# v2-DCSupplyHub.net
KiCad netlist of a schematic drawn in Altium Designer
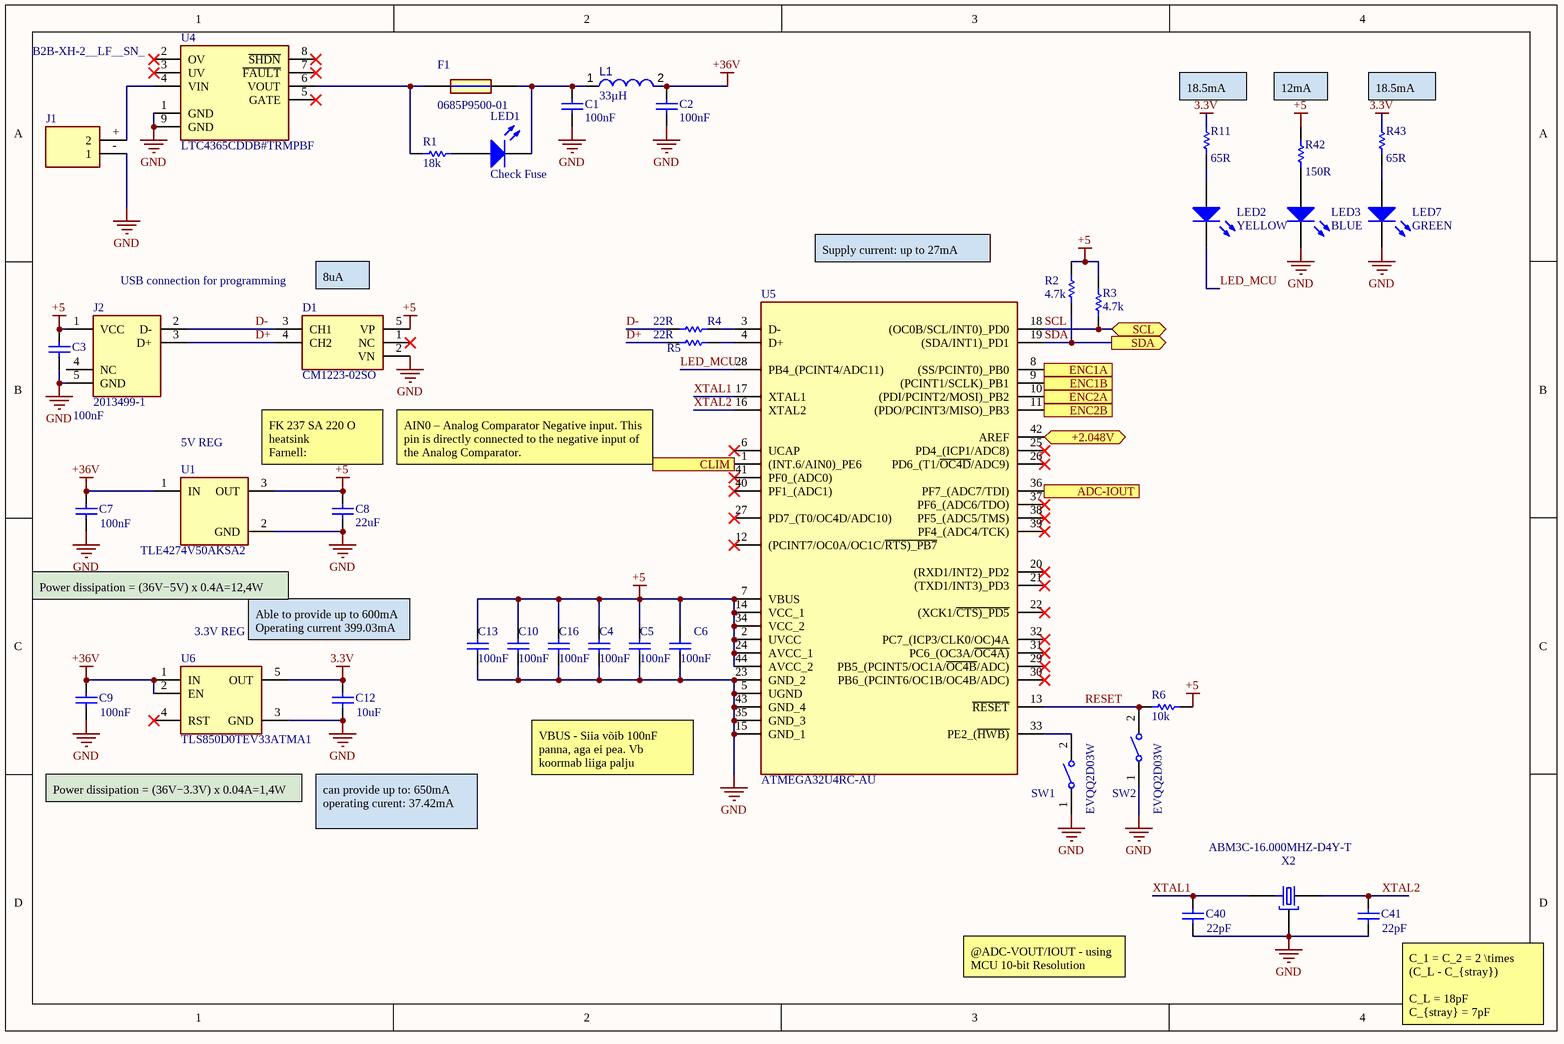
[diagram p0: v2-DCSupplyHub.SchDoc]

(export (version "E")
  (design (tool "Eeschema 10.0.6"))
  (components
    (comp (ref "C1")
      (value "100nF")
      (footprint "Cap_0603")
      (description "Capacitor")
      (fields (field (name "Comment") "Cap") (field (name "PUBLISHER") "Altium Limited"))
      (libsource (lib "cc cv power supply") (part "Cap"))
    )
    (comp (ref "C2")
      (value "100nF")
      (footprint "Cap_0603")
      (description "Capacitor")
      (fields (field (name "Comment") "Cap") (field (name "PUBLISHER") "Altium Limited"))
      (libsource (lib "cc cv power supply") (part "Cap"))
    )
    (comp (ref "C3")
      (value "100nF")
      (footprint "Cap_0603")
      (description "Capacitor")
      (fields (field (name "Comment") "Cap") (field (name "PUBLISHER") "Altium Limited"))
      (libsource (lib "cc cv power supply") (part "Cap"))
    )
    (comp (ref "C4")
      (value "100nF")
      (footprint "Cap_0603")
      (description "Capacitor")
      (fields (field (name "Comment") "Cap") (field (name "PUBLISHER") "Altium Limited"))
      (libsource (lib "cc cv power supply") (part "Cap"))
    )
    (comp (ref "C5")
      (value "100nF")
      (footprint "Cap_0603")
      (description "Capacitor")
      (fields (field (name "Comment") "Cap") (field (name "PUBLISHER") "Altium Limited"))
      (libsource (lib "cc cv power supply") (part "Cap"))
    )
    (comp (ref "C6")
      (value "100nF")
      (footprint "Cap_0603")
      (description "Capacitor")
      (fields (field (name "Comment") "Cap") (field (name "PUBLISHER") "Altium Limited"))
      (libsource (lib "cc cv power supply") (part "Cap"))
    )
    (comp (ref "C7")
      (value "100nF")
      (footprint "Cap_0603")
      (description "Capacitor")
      (fields (field (name "Comment") "Cap") (field (name "PUBLISHER") "Altium Limited"))
      (libsource (lib "cc cv power supply") (part "Cap"))
    )
    (comp (ref "C8")
      (value "22uF")
      (footprint "Cap_0603")
      (description "Capacitor")
      (fields (field (name "Comment") "Cap") (field (name "PUBLISHER") "Altium Limited"))
      (libsource (lib "cc cv power supply") (part "Cap"))
    )
    (comp (ref "C9")
      (value "100nF")
      (footprint "Cap_0603")
      (description "Capacitor")
      (fields (field (name "Comment") "Cap") (field (name "PUBLISHER") "Altium Limited"))
      (libsource (lib "cc cv power supply") (part "Cap"))
    )
    (comp (ref "C10")
      (value "100nF")
      (footprint "Cap_0603")
      (description "Capacitor")
      (fields (field (name "Comment") "Cap") (field (name "PUBLISHER") "Altium Limited"))
      (libsource (lib "cc cv power supply") (part "Cap"))
    )
    (comp (ref "C12")
      (value "10uF")
      (footprint "Cap_0603")
      (description "Capacitor")
      (fields (field (name "Comment") "Cap") (field (name "PUBLISHER") "Altium Limited"))
      (libsource (lib "cc cv power supply") (part "Cap"))
    )
    (comp (ref "C13")
      (value "100nF")
      (footprint "Cap_0603")
      (description "Capacitor")
      (fields (field (name "Comment") "Cap") (field (name "PUBLISHER") "Altium Limited"))
      (libsource (lib "cc cv power supply") (part "Cap"))
    )
    (comp (ref "C16")
      (value "100nF")
      (footprint "Cap_0603")
      (description "Capacitor")
      (fields (field (name "Comment") "Cap") (field (name "PUBLISHER") "Altium Limited"))
      (libsource (lib "cc cv power supply") (part "Cap"))
    )
    (comp (ref "C40")
      (value "22pF")
      (footprint "Cap_0603")
      (description "Capacitor")
      (fields (field (name "Comment") "Cap") (field (name "PUBLISHER") "Altium Limited"))
      (libsource (lib "cc cv power supply") (part "Cap"))
    )
    (comp (ref "C41")
      (value "22pF")
      (footprint "Cap_0603")
      (description "Capacitor")
      (fields (field (name "Comment") "Cap") (field (name "PUBLISHER") "Altium Limited"))
      (libsource (lib "cc cv power supply") (part "Cap"))
    )
    (comp (ref "D1")
      (value "CM1223-02SO")
      (footprint "SamacSys:SOT95P280X145-5N")
      (description "TVS Diode (Uni-directional)")
      (fields (field (name "MOUSER PART NUMBER") "748-CM1223-02SO"))
      (libsource (lib "SamacSys") (part "CM1223-02SO"))
    )
    (comp (ref "F1")
      (value "0685P9500-01")
      (footprint "FUSC3216X83N")
      (description "Fuse Chip Fast Acting 50A 32V SMD Solder Pad 1206 3.2 X 1.58 X 0.63mm Ceramic T/R")
      (libsource (lib "DCSupplyHubLib") (part "0685P9500-01"))
    )
    (comp (ref "J1")
      (value "B2B-XH-2__LF__SN_")
      (footprint "SamacSys:B2BXH2LFSN")
      (description "Connector")
      (fields (field (name "MANUFACTURER_PART_NUMBER") "B2B-XH-2 (LF)(SN)"))
      (libsource (lib "DCSupplyHubLib") (part "B2B-XH-2__LF__SN_"))
    )
    (comp (ref "J2")
      (value "2013499-1")
      (footprint "SamacSys:2013499-1")
      (description "Connector")
      (fields (field (name "MOUSER PART NUMBER") "571-2013499-1"))
      (libsource (lib "SamacSys") (part "2013499-1"))
    )
    (comp (ref "L1")
      (value "33µH")
      (footprint "WE-LQS 4018")
      (description "WE-LQS SMD Power Inductor, L=33 µH")
      (fields (field (name "TOLERANCE") "20%") (field (name "Comment") "74404042330"))
      (libsource (lib "University of Tartu") (part "CMP-001-0020-1"))
    )
    (comp (ref "LED1")
      (value "Check Fuse")
      (footprint "LED_SMD_0805_R")
      (description "Typical RED, GREEN, YELLOW, AMBER GaAs LED")
      (fields (field (name "PUBLISHER") "Altium Limited"))
      (libsource (lib "cc cv power supply") (part "LED2"))
    )
    (comp (ref "LED2")
      (value "YELLOW")
      (footprint "LED_SMD_0805_R")
      (description "Typical RED, GREEN, YELLOW, AMBER GaAs LED")
      (fields (field (name "PUBLISHER") "Altium Limited"))
      (libsource (lib "cc cv power supply") (part "LED2"))
    )
    (comp (ref "LED3")
      (value "BLUE")
      (footprint "LED_SMD_0805_R")
      (description "Typical RED, GREEN, YELLOW, AMBER GaAs LED")
      (fields (field (name "PUBLISHER") "Altium Limited"))
      (libsource (lib "cc cv power supply") (part "LED2"))
    )
    (comp (ref "LED7")
      (value "GREEN")
      (footprint "LED_SMD_0805_R")
      (description "Typical RED, GREEN, YELLOW, AMBER GaAs LED")
      (fields (field (name "PUBLISHER") "Altium Limited"))
      (libsource (lib "cc cv power supply") (part "LED2"))
    )
    (comp (ref "R1")
      (value "18k")
      (footprint "RES_0805")
      (description "Resistor")
      (fields (field (name "Comment") "Res1") (field (name "PUBLISHER") "Altium Limited"))
      (libsource (lib "cc cv power supply") (part "Res1"))
    )
    (comp (ref "R2")
      (value "4.7k")
      (footprint "RES_0805")
      (description "Resistor")
      (fields (field (name "Comment") "Res1") (field (name "PUBLISHER") "Altium Limited"))
      (libsource (lib "cc cv power supply") (part "Res1"))
    )
    (comp (ref "R3")
      (value "4.7k")
      (footprint "RES_0805")
      (description "Resistor")
      (fields (field (name "Comment") "Res1") (field (name "PUBLISHER") "Altium Limited"))
      (libsource (lib "cc cv power supply") (part "Res1"))
    )
    (comp (ref "R4")
      (value "22R")
      (footprint "RES_0805")
      (description "Resistor")
      (fields (field (name "Comment") "Res1") (field (name "PUBLISHER") "Altium Limited"))
      (libsource (lib "cc cv power supply") (part "Res1"))
    )
    (comp (ref "R5")
      (value "22R")
      (footprint "RES_0805")
      (description "Resistor")
      (fields (field (name "Comment") "Res1") (field (name "PUBLISHER") "Altium Limited"))
      (libsource (lib "cc cv power supply") (part "Res1"))
    )
    (comp (ref "R6")
      (value "10k")
      (footprint "RES_0805")
      (description "Resistor")
      (fields (field (name "Comment") "Res1") (field (name "PUBLISHER") "Altium Limited"))
      (libsource (lib "cc cv power supply") (part "Res1"))
    )
    (comp (ref "R11")
      (value "65R")
      (footprint "RES_0805")
      (description "Resistor")
      (fields (field (name "Comment") "Res1") (field (name "PUBLISHER") "Altium Limited"))
      (libsource (lib "cc cv power supply") (part "Res1"))
    )
    (comp (ref "R42")
      (value "150R")
      (footprint "RES_0805")
      (description "Resistor")
      (fields (field (name "Comment") "Res1") (field (name "PUBLISHER") "Altium Limited"))
      (libsource (lib "cc cv power supply") (part "Res1"))
    )
    (comp (ref "R43")
      (value "65R")
      (footprint "RES_0805")
      (description "Resistor")
      (fields (field (name "Comment") "Res1") (field (name "PUBLISHER") "Altium Limited"))
      (libsource (lib "cc cv power supply") (part "Res1"))
    )
    (comp (ref "SW1")
      (value "EVQQ2D03W")
      (footprint "EVQQ2D03W")
      (description "FSMSM Push Button Switch, 50 mA, -35 to 85 degC, 2-Pin SMD, RoHS, Tape and Reel")
      (fields (field (name "MANUFACTURER") "TE Connectivity"))
      (libsource (lib "DCSupplyHubLib") (part "SW-SPST-2_C"))
    )
    (comp (ref "SW2")
      (value "EVQQ2D03W")
      (footprint "EVQQ2D03W")
      (description "FSMSM Push Button Switch, 50 mA, -35 to 85 degC, 2-Pin SMD, RoHS, Tape and Reel")
      (fields (field (name "MANUFACTURER") "TE Connectivity"))
      (libsource (lib "DCSupplyHubLib") (part "SW-SPST-2_C"))
    )
    (comp (ref "U1")
      (value "TLE4274V50AKSA2")
      (footprint "TO254P440X1000X2110-3P")
      (description "LDO, FIXED, 5V, 0.4A, -40 TO 150DEG C")
      (fields
        (field (name "MANUFACTURER_PART_NUMBER") "TLE4274DV50ATMA2")
        (field (name "MOUSER PART NUMBER") "726-TLE4274DV50ATMA2")
      )
      (libsource (lib "SamacSys") (part "TLE4274DV50ATMA2"))
    )
    (comp (ref "U4")
      (value "LTC4365CDDB#PBF")
      (footprint "SamacSys:SON50P200X300X80-9N-D")
      (description "vervoltage, Undervoltage and Reverse Supply Protection Controller")
      (fields (field (name "MOUSER PART NUMBER") "584-LTC4365CDDB#PBF"))
      (libsource (lib "DCSupplyHubLib") (part "LTC4365CDDB#PBF"))
    )
    (comp (ref "U5")
      (value "ATMEGA32U4-AU")
      (footprint "QFP80P1200X1200X120-44N")
      (fields (field (name "MOUSER PART NUMBER") "556-ATMEGA32U4-AU"))
      (libsource (lib "DCSupplyHubLib") (part "ATMEGA32U4-AU"))
    )
    (comp (ref "U6")
      (value "TLS850D0TEV33ATMA1")
      (footprint "SamacSys:BTS6143D")
      (description "LDO VOltage regulator")
      (fields (field (name "MOUSER PART NUMBER") "726-TLS850D0TEV33ATM"))
      (libsource (lib "SamacSys") (part "TLS850D0TEV33ATMA1"))
    )
    (comp (ref "X2")
      (value "ABM3C-16.000MHZ-D4Y-T")
      (footprint "ABM3C16000MHZD4YT")
      (description "16MHz Â±30ppm Crystal 18pF 50 Ohms 4-SMD, No Lead")
      (fields (field (name "MF") "Abracon"))
      (libsource (lib "cc cv power supply") (part "ABM3C-16.000MHZ-D4Y-T"))
    )
  )
  (nets
    (net (code "1") (name "+5") (class "Default")
      (node (ref "C10") (pin "2") (pinfunction "2_2") (pintype "passive"))
      (node (ref "C13") (pin "2") (pinfunction "2_2") (pintype "passive"))
      (node (ref "C16") (pin "2") (pinfunction "2_2") (pintype "passive"))
      (node (ref "C3") (pin "2") (pinfunction "2_2") (pintype "passive"))
      (node (ref "C4") (pin "2") (pinfunction "2_2") (pintype "passive"))
      (node (ref "C5") (pin "2") (pinfunction "2_2") (pintype "passive"))
      (node (ref "C6") (pin "2") (pinfunction "2_2") (pintype "passive"))
      (node (ref "C8") (pin "1") (pinfunction "1_1") (pintype "passive"))
      (node (ref "D1") (pin "5") (pinfunction "VP_5") (pintype "passive"))
      (node (ref "J2") (pin "1") (pinfunction "VCC_1") (pintype "passive"))
      (node (ref "R2") (pin "2") (pinfunction "2_2") (pintype "passive"))
      (node (ref "R3") (pin "2") (pinfunction "2_2") (pintype "passive"))
      (node (ref "R42") (pin "1") (pinfunction "1_1") (pintype "passive"))
      (node (ref "R6") (pin "1") (pinfunction "1_1") (pintype "passive"))
      (node (ref "U1") (pin "3") (pinfunction "OUT_3") (pintype "passive"))
      (node (ref "U5") (pin "14") (pinfunction "VCC_1_14") (pintype "passive"))
      (node (ref "U5") (pin "2") (pinfunction "UVCC_2") (pintype "passive"))
      (node (ref "U5") (pin "24") (pinfunction "AVCC_1_24") (pintype "passive"))
      (node (ref "U5") (pin "34") (pinfunction "VCC_2_34") (pintype "passive"))
      (node (ref "U5") (pin "44") (pinfunction "AVCC_2_44") (pintype "passive"))
      (node (ref "U5") (pin "7") (pinfunction "VBUS_7") (pintype "passive"))
    )
    (net (code "2") (name "+36V") (class "Default")
      (node (ref "C2") (pin "1") (pinfunction "1_1") (pintype "passive"))
      (node (ref "C7") (pin "2") (pinfunction "2_2") (pintype "passive"))
      (node (ref "C9") (pin "2") (pinfunction "2_2") (pintype "passive"))
      (node (ref "L1") (pin "2") (pinfunction "2_2") (pintype "passive"))
      (node (ref "U1") (pin "1") (pinfunction "IN_1") (pintype "passive"))
      (node (ref "U6") (pin "1") (pinfunction "IN_1") (pintype "passive"))
      (node (ref "U6") (pin "2") (pinfunction "EN_2") (pintype "passive"))
    )
    (net (code "3") (name "/+2.048V") (class "Default")
      (node (ref "U5") (pin "42") (pinfunction "AREF_42") (pintype "passive"))
    )
    (net (code "4") (name "/ADC-IOUT") (class "Default")
      (node (ref "U5") (pin "36") (pinfunction "PF7_(ADC7/TDI)_36") (pintype "passive"))
    )
    (net (code "5") (name "/CLIM") (class "Default")
      (node (ref "U5") (pin "1") (pinfunction "(INT.6/AIN0)_PE6_1") (pintype "passive"))
    )
    (net (code "6") (name "/D+") (class "Default")
      (node (ref "D1") (pin "4") (pinfunction "CH2_4") (pintype "passive"))
      (node (ref "J2") (pin "3") (pinfunction "D+_3") (pintype "passive"))
      (node (ref "R5") (pin "2") (pinfunction "2_2") (pintype "passive"))
    )
    (net (code "7") (name "/D-") (class "Default")
      (node (ref "D1") (pin "3") (pinfunction "CH1_3") (pintype "passive"))
      (node (ref "J2") (pin "2") (pinfunction "D-_2") (pintype "passive"))
      (node (ref "R4") (pin "2") (pinfunction "2_2") (pintype "passive"))
    )
    (net (code "8") (name "/ENC1A") (class "Default")
      (node (ref "U5") (pin "8") (pinfunction "(SS/PCINT0)_PB0_8") (pintype "passive"))
    )
    (net (code "9") (name "/ENC1B") (class "Default")
      (node (ref "U5") (pin "9") (pinfunction "(PCINT1/SCLK)_PB1_9") (pintype "passive"))
    )
    (net (code "10") (name "/ENC2A") (class "Default")
      (node (ref "U5") (pin "10") (pinfunction "(PDI/PCINT2/MOSI)_PB2_10") (pintype "passive"))
    )
    (net (code "11") (name "/ENC2B") (class "Default")
      (node (ref "U5") (pin "11") (pinfunction "(PDO/PCINT3/MISO)_PB3_11") (pintype "passive"))
    )
    (net (code "12") (name "/LED_MCU") (class "Default")
      (node (ref "LED2") (pin "2") (pinfunction "K_2") (pintype "passive"))
      (node (ref "U5") (pin "28") (pinfunction "PB4_(PCINT4/ADC11)_28") (pintype "passive"))
    )
    (net (code "13") (name "/RESET") (class "Default")
      (node (ref "R6") (pin "2") (pinfunction "2_2") (pintype "passive"))
      (node (ref "SW2") (pin "2") (pinfunction "2_2") (pintype "passive"))
      (node (ref "U5") (pin "13") (pinfunction "~{RESET}_13") (pintype "passive"))
    )
    (net (code "14") (name "/SCL") (class "Default")
      (node (ref "R3") (pin "1") (pinfunction "1_1") (pintype "passive"))
      (node (ref "U5") (pin "18") (pinfunction "(OC0B/SCL/INT0)_PD0_18") (pintype "passive"))
    )
    (net (code "15") (name "/SDA") (class "Default")
      (node (ref "R2") (pin "1") (pinfunction "1_1") (pintype "passive"))
      (node (ref "U5") (pin "19") (pinfunction "(SDA/INT1)_PD1_19") (pintype "passive"))
    )
    (net (code "16") (name "/XTAL1") (class "Default")
      (node (ref "C40") (pin "2") (pinfunction "2_2") (pintype "passive"))
      (node (ref "U5") (pin "17") (pinfunction "XTAL1_17") (pintype "passive"))
      (node (ref "X2") (pin "1") (pinfunction "1_1") (pintype "passive"))
    )
    (net (code "17") (name "/XTAL2") (class "Default")
      (node (ref "C41") (pin "2") (pinfunction "2_2") (pintype "passive"))
      (node (ref "U5") (pin "16") (pinfunction "XTAL2_16") (pintype "passive"))
      (node (ref "X2") (pin "3") (pinfunction "3_3") (pintype "passive"))
    )
    (net (code "18") (name "3.3V") (class "Default")
      (node (ref "C12") (pin "2") (pinfunction "2_2") (pintype "passive"))
      (node (ref "R11") (pin "1") (pinfunction "1_1") (pintype "passive"))
      (node (ref "R43") (pin "1") (pinfunction "1_1") (pintype "passive"))
      (node (ref "U6") (pin "5") (pinfunction "OUT_5") (pintype "passive"))
    )
    (net (code "19") (name "GND") (class "Default")
      (node (ref "C1") (pin "2") (pinfunction "2_2") (pintype "passive"))
      (node (ref "C10") (pin "1") (pinfunction "1_1") (pintype "passive"))
      (node (ref "C12") (pin "1") (pinfunction "1_1") (pintype "passive"))
      (node (ref "C13") (pin "1") (pinfunction "1_1") (pintype "passive"))
      (node (ref "C16") (pin "1") (pinfunction "1_1") (pintype "passive"))
      (node (ref "C2") (pin "2") (pinfunction "2_2") (pintype "passive"))
      (node (ref "C3") (pin "1") (pinfunction "1_1") (pintype "passive"))
      (node (ref "C4") (pin "1") (pinfunction "1_1") (pintype "passive"))
      (node (ref "C40") (pin "1") (pinfunction "1_1") (pintype "passive"))
      (node (ref "C41") (pin "1") (pinfunction "1_1") (pintype "passive"))
      (node (ref "C5") (pin "1") (pinfunction "1_1") (pintype "passive"))
      (node (ref "C6") (pin "1") (pinfunction "1_1") (pintype "passive"))
      (node (ref "C7") (pin "1") (pinfunction "1_1") (pintype "passive"))
      (node (ref "C8") (pin "2") (pinfunction "2_2") (pintype "passive"))
      (node (ref "C9") (pin "1") (pinfunction "1_1") (pintype "passive"))
      (node (ref "D1") (pin "2") (pinfunction "VN_2") (pintype "passive"))
      (node (ref "J1") (pin "-") (pinfunction "1_-") (pintype "passive"))
      (node (ref "J2") (pin "5") (pinfunction "GND_5") (pintype "passive"))
      (node (ref "LED3") (pin "2") (pinfunction "K_2") (pintype "passive"))
      (node (ref "LED7") (pin "2") (pinfunction "K_2") (pintype "passive"))
      (node (ref "SW1") (pin "1") (pinfunction "1_1") (pintype "passive"))
      (node (ref "SW2") (pin "1") (pinfunction "1_1") (pintype "passive"))
      (node (ref "U1") (pin "2") (pinfunction "GND_2") (pintype "passive"))
      (node (ref "U4") (pin "1") (pinfunction "GND_1") (pintype "passive"))
      (node (ref "U4") (pin "9") (pinfunction "GND_9") (pintype "passive"))
      (node (ref "U5") (pin "15") (pinfunction "GND_1_15") (pintype "passive"))
      (node (ref "U5") (pin "23") (pinfunction "GND_2_23") (pintype "passive"))
      (node (ref "U5") (pin "35") (pinfunction "GND_3_35") (pintype "passive"))
      (node (ref "U5") (pin "43") (pinfunction "GND_4_43") (pintype "passive"))
      (node (ref "U5") (pin "5") (pinfunction "UGND_5") (pintype "passive"))
      (node (ref "U6") (pin "3") (pinfunction "GND_3") (pintype "passive"))
      (node (ref "X2") (pin "2") (pinfunction "GND_2") (pintype "passive"))
      (node (ref "X2") (pin "4") (pinfunction "GND_4") (pintype "passive"))
    )
    (net (code "20") (name "Net-(J1-2)") (class "Default")
      (node (ref "J1") (pin "+") (pinfunction "2_+") (pintype "passive"))
      (node (ref "U4") (pin "4") (pinfunction "VIN_4") (pintype "passive"))
    )
    (net (code "21") (name "Net-(LED1-A)") (class "Default")
      (node (ref "LED1") (pin "1") (pinfunction "A_1") (pintype "passive"))
      (node (ref "R1") (pin "1") (pinfunction "1_1") (pintype "passive"))
    )
    (net (code "22") (name "Net-(LED1-K)") (class "Default")
      (node (ref "C1") (pin "1") (pinfunction "1_1") (pintype "passive"))
      (node (ref "F1") (pin "2") (pinfunction "2_2") (pintype "passive"))
      (node (ref "L1") (pin "1") (pinfunction "1_1") (pintype "passive"))
      (node (ref "LED1") (pin "2") (pinfunction "K_2") (pintype "passive"))
    )
    (net (code "23") (name "Net-(LED2-A)") (class "Default")
      (node (ref "LED2") (pin "1") (pinfunction "A_1") (pintype "passive"))
      (node (ref "R11") (pin "2") (pinfunction "2_2") (pintype "passive"))
    )
    (net (code "24") (name "Net-(LED3-A)") (class "Default")
      (node (ref "LED3") (pin "1") (pinfunction "A_1") (pintype "passive"))
      (node (ref "R42") (pin "2") (pinfunction "2_2") (pintype "passive"))
    )
    (net (code "25") (name "Net-(LED7-A)") (class "Default")
      (node (ref "LED7") (pin "1") (pinfunction "A_1") (pintype "passive"))
      (node (ref "R43") (pin "2") (pinfunction "2_2") (pintype "passive"))
    )
    (net (code "26") (name "Net-(U4-VOUT)") (class "Default")
      (node (ref "F1") (pin "1") (pinfunction "1_1") (pintype "passive"))
      (node (ref "R1") (pin "2") (pinfunction "2_2") (pintype "passive"))
      (node (ref "U4") (pin "6") (pinfunction "VOUT_6") (pintype "passive"))
    )
    (net (code "27") (name "Net-(U5-D+)") (class "Default")
      (node (ref "R5") (pin "1") (pinfunction "1_1") (pintype "passive"))
      (node (ref "U5") (pin "4") (pinfunction "D+_4") (pintype "passive"))
    )
    (net (code "28") (name "Net-(U5-D-)") (class "Default")
      (node (ref "R4") (pin "1") (pinfunction "1_1") (pintype "passive"))
      (node (ref "U5") (pin "3") (pinfunction "D-_3") (pintype "passive"))
    )
    (net (code "29") (name "Net-(U5-PE2_(~{HWB)})") (class "Default")
      (node (ref "SW1") (pin "2") (pinfunction "2_2") (pintype "passive"))
      (node (ref "U5") (pin "33") (pinfunction "PE2_(~{HWB)}_33") (pintype "passive"))
    )
    (net (code "30") (name "unconnected-(D1-NC-Pad1)") (class "Default")
      (node (ref "D1") (pin "1") (pinfunction "NC_1") (pintype "passive+no_connect"))
    )
    (net (code "31") (name "unconnected-(J2-NC-Pad4)") (class "Default")
      (node (ref "J2") (pin "4") (pinfunction "NC_4") (pintype "passive"))
    )
    (net (code "32") (name "unconnected-(U4-GATE-Pad5)") (class "Default")
      (node (ref "U4") (pin "5") (pinfunction "GATE_5") (pintype "passive+no_connect"))
    )
    (net (code "33") (name "unconnected-(U4-OV-Pad2)") (class "Default")
      (node (ref "U4") (pin "2") (pinfunction "OV_2") (pintype "passive+no_connect"))
    )
    (net (code "34") (name "unconnected-(U4-UV-Pad3)") (class "Default")
      (node (ref "U4") (pin "3") (pinfunction "UV_3") (pintype "passive+no_connect"))
    )
    (net (code "35") (name "unconnected-(U4-~{FAULT}-Pad7)") (class "Default")
      (node (ref "U4") (pin "7") (pinfunction "~{FAULT}_7") (pintype "passive+no_connect"))
    )
    (net (code "36") (name "unconnected-(U4-~{SHDN}-Pad8)") (class "Default")
      (node (ref "U4") (pin "8") (pinfunction "~{SHDN}_8") (pintype "passive+no_connect"))
    )
    (net (code "37") (name "unconnected-(U5-(PCINT7{slash}OC0A{slash}OC1C{slash}~{RTS)_PB7}-Pad12)") (class "Default")
      (node (ref "U5") (pin "12") (pinfunction "(PCINT7/OC0A/OC1C/~{RTS)_PB7}_12") (pintype "passive+no_connect"))
    )
    (net (code "38") (name "unconnected-(U5-(RXD1{slash}INT2)_PD2-Pad20)") (class "Default")
      (node (ref "U5") (pin "20") (pinfunction "(RXD1/INT2)_PD2_20") (pintype "passive+no_connect"))
    )
    (net (code "39") (name "unconnected-(U5-(TXD1{slash}INT3)_PD3-Pad21)") (class "Default")
      (node (ref "U5") (pin "21") (pinfunction "(TXD1/INT3)_PD3_21") (pintype "passive+no_connect"))
    )
    (net (code "40") (name "unconnected-(U5-(XCK1{slash}~{CTS)_PD5}-Pad22)") (class "Default")
      (node (ref "U5") (pin "22") (pinfunction "(XCK1/~{CTS)_PD5}_22") (pintype "passive+no_connect"))
    )
    (net (code "41") (name "unconnected-(U5-PB5_(PCINT5{slash}OC1A{slash}~{OC4B}{slash}ADC)-Pad29)") (class "Default")
      (node (ref "U5") (pin "29") (pinfunction "PB5_(PCINT5/OC1A/~{OC4B}/ADC)_29") (pintype "passive+no_connect"))
    )
    (net (code "42") (name "unconnected-(U5-PB6_(PCINT6{slash}OC1B{slash}OC4B{slash}ADC)-Pad30)") (class "Default")
      (node (ref "U5") (pin "30") (pinfunction "PB6_(PCINT6/OC1B/OC4B/ADC)_30") (pintype "passive+no_connect"))
    )
    (net (code "43") (name "unconnected-(U5-PC6_(OC3A{slash}~{OC4A)}-Pad31)") (class "Default")
      (node (ref "U5") (pin "31") (pinfunction "PC6_(OC3A/~{OC4A)}_31") (pintype "passive+no_connect"))
    )
    (net (code "44") (name "unconnected-(U5-PC7_(ICP3{slash}CLK0{slash}OC)4A-Pad32)") (class "Default")
      (node (ref "U5") (pin "32") (pinfunction "PC7_(ICP3/CLK0/OC)4A_32") (pintype "passive+no_connect"))
    )
    (net (code "45") (name "unconnected-(U5-PD4_(ICP1{slash}ADC8)-Pad25)") (class "Default")
      (node (ref "U5") (pin "25") (pinfunction "PD4_(ICP1/ADC8)_25") (pintype "passive+no_connect"))
    )
    (net (code "46") (name "unconnected-(U5-PD6_(T1{slash}~{OC4D}{slash}ADC9)-Pad26)") (class "Default")
      (node (ref "U5") (pin "26") (pinfunction "PD6_(T1/~{OC4D}/ADC9)_26") (pintype "passive+no_connect"))
    )
    (net (code "47") (name "unconnected-(U5-PD7_(T0{slash}OC4D{slash}ADC10)-Pad27)") (class "Default")
      (node (ref "U5") (pin "27") (pinfunction "PD7_(T0/OC4D/ADC10)_27") (pintype "passive+no_connect"))
    )
    (net (code "48") (name "unconnected-(U5-PF0_(ADC0)-Pad41)") (class "Default")
      (node (ref "U5") (pin "41") (pinfunction "PF0_(ADC0)_41") (pintype "passive+no_connect"))
    )
    (net (code "49") (name "unconnected-(U5-PF1_(ADC1)-Pad40)") (class "Default")
      (node (ref "U5") (pin "40") (pinfunction "PF1_(ADC1)_40") (pintype "passive+no_connect"))
    )
    (net (code "50") (name "unconnected-(U5-PF4_(ADC4{slash}TCK)-Pad39)") (class "Default")
      (node (ref "U5") (pin "39") (pinfunction "PF4_(ADC4/TCK)_39") (pintype "passive+no_connect"))
    )
    (net (code "51") (name "unconnected-(U5-PF5_(ADC5{slash}TMS)-Pad38)") (class "Default")
      (node (ref "U5") (pin "38") (pinfunction "PF5_(ADC5/TMS)_38") (pintype "passive+no_connect"))
    )
    (net (code "52") (name "unconnected-(U5-PF6_(ADC6{slash}TDO)-Pad37)") (class "Default")
      (node (ref "U5") (pin "37") (pinfunction "PF6_(ADC6/TDO)_37") (pintype "passive+no_connect"))
    )
    (net (code "53") (name "unconnected-(U5-UCAP-Pad6)") (class "Default")
      (node (ref "U5") (pin "6") (pinfunction "UCAP_6") (pintype "passive+no_connect"))
    )
    (net (code "54") (name "unconnected-(U6-RST-Pad4)") (class "Default")
      (node (ref "U6") (pin "4") (pinfunction "RST_4") (pintype "passive+no_connect"))
    )
  )
)
